# Pots.net
KiCad netlist of a schematic drawn in EAGLE
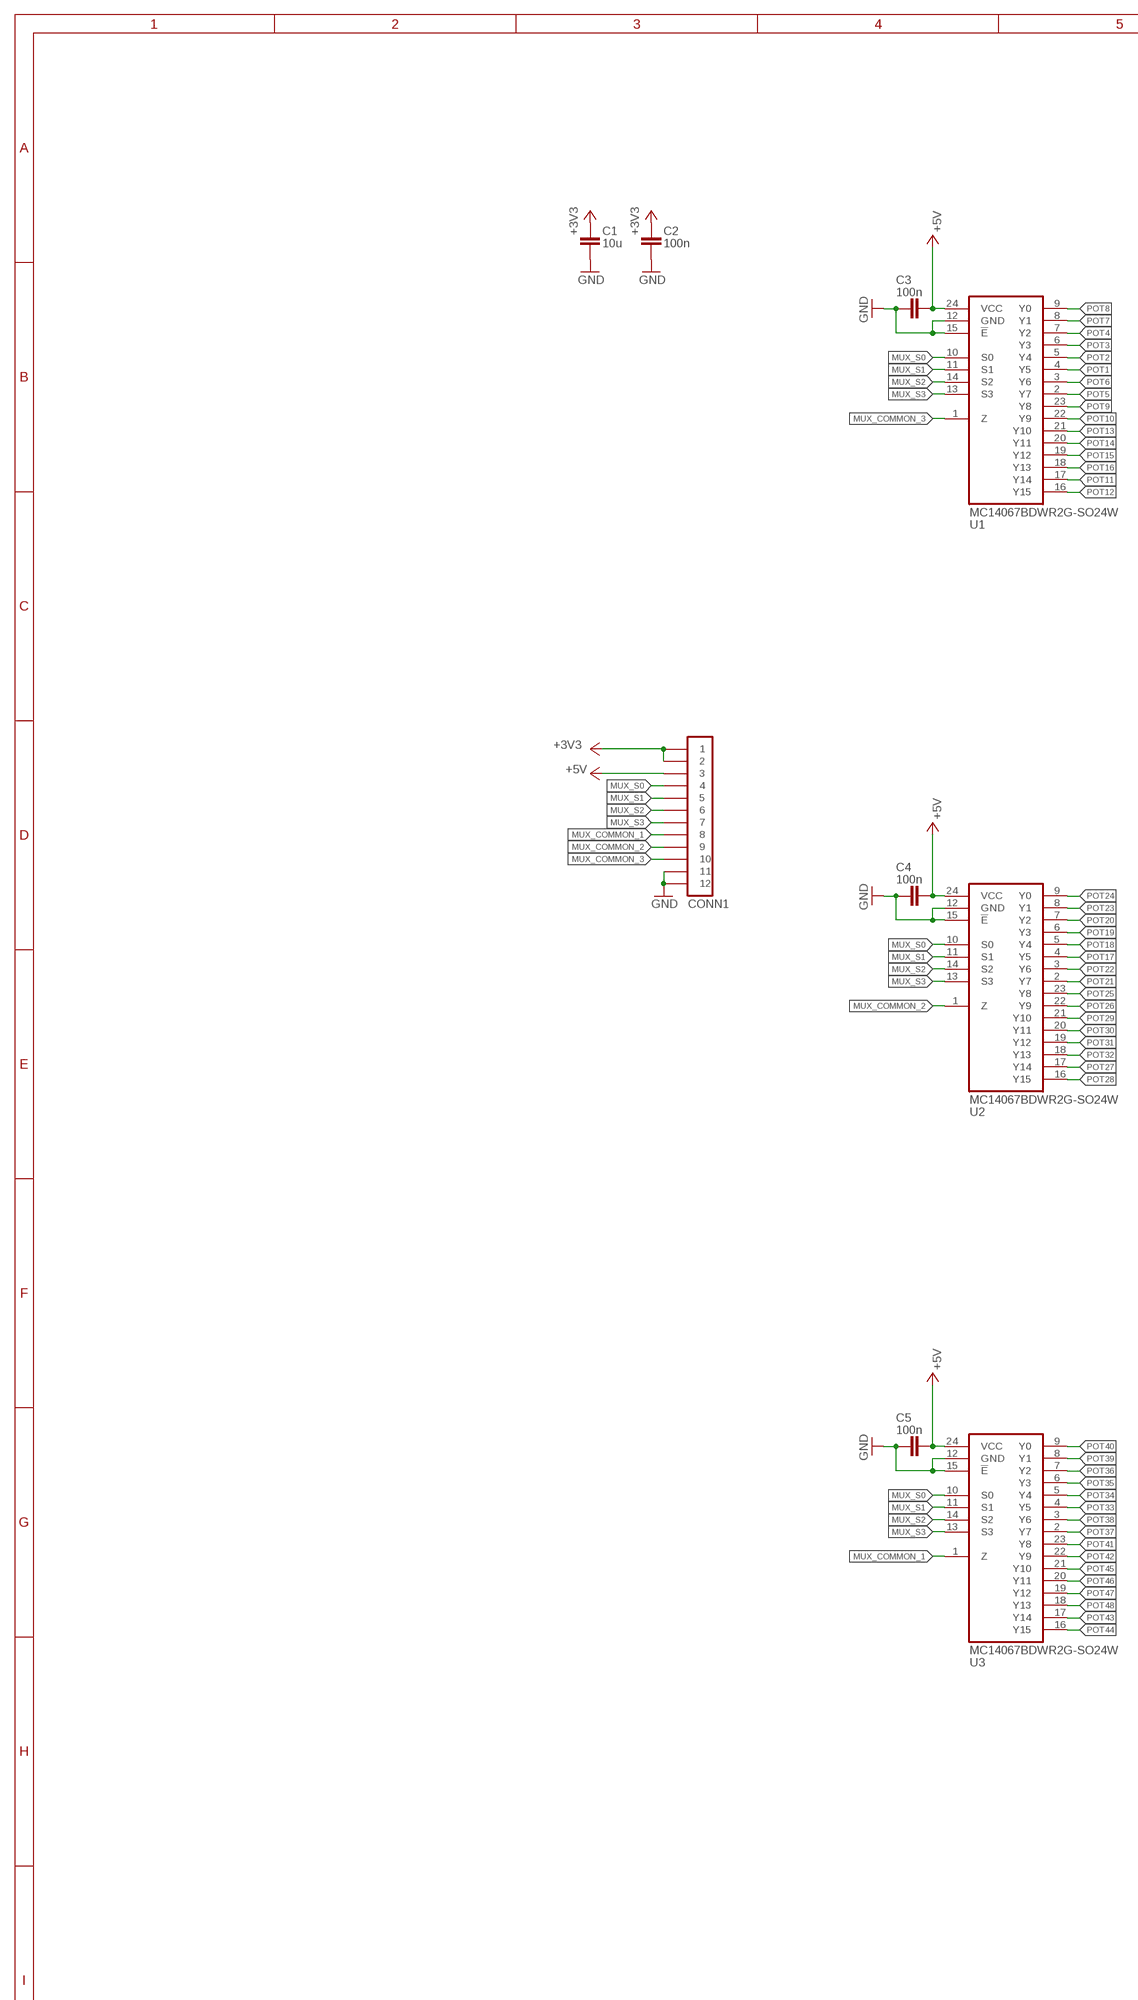
[diagram p0: schematic, sheet 1, part 1 of 2]
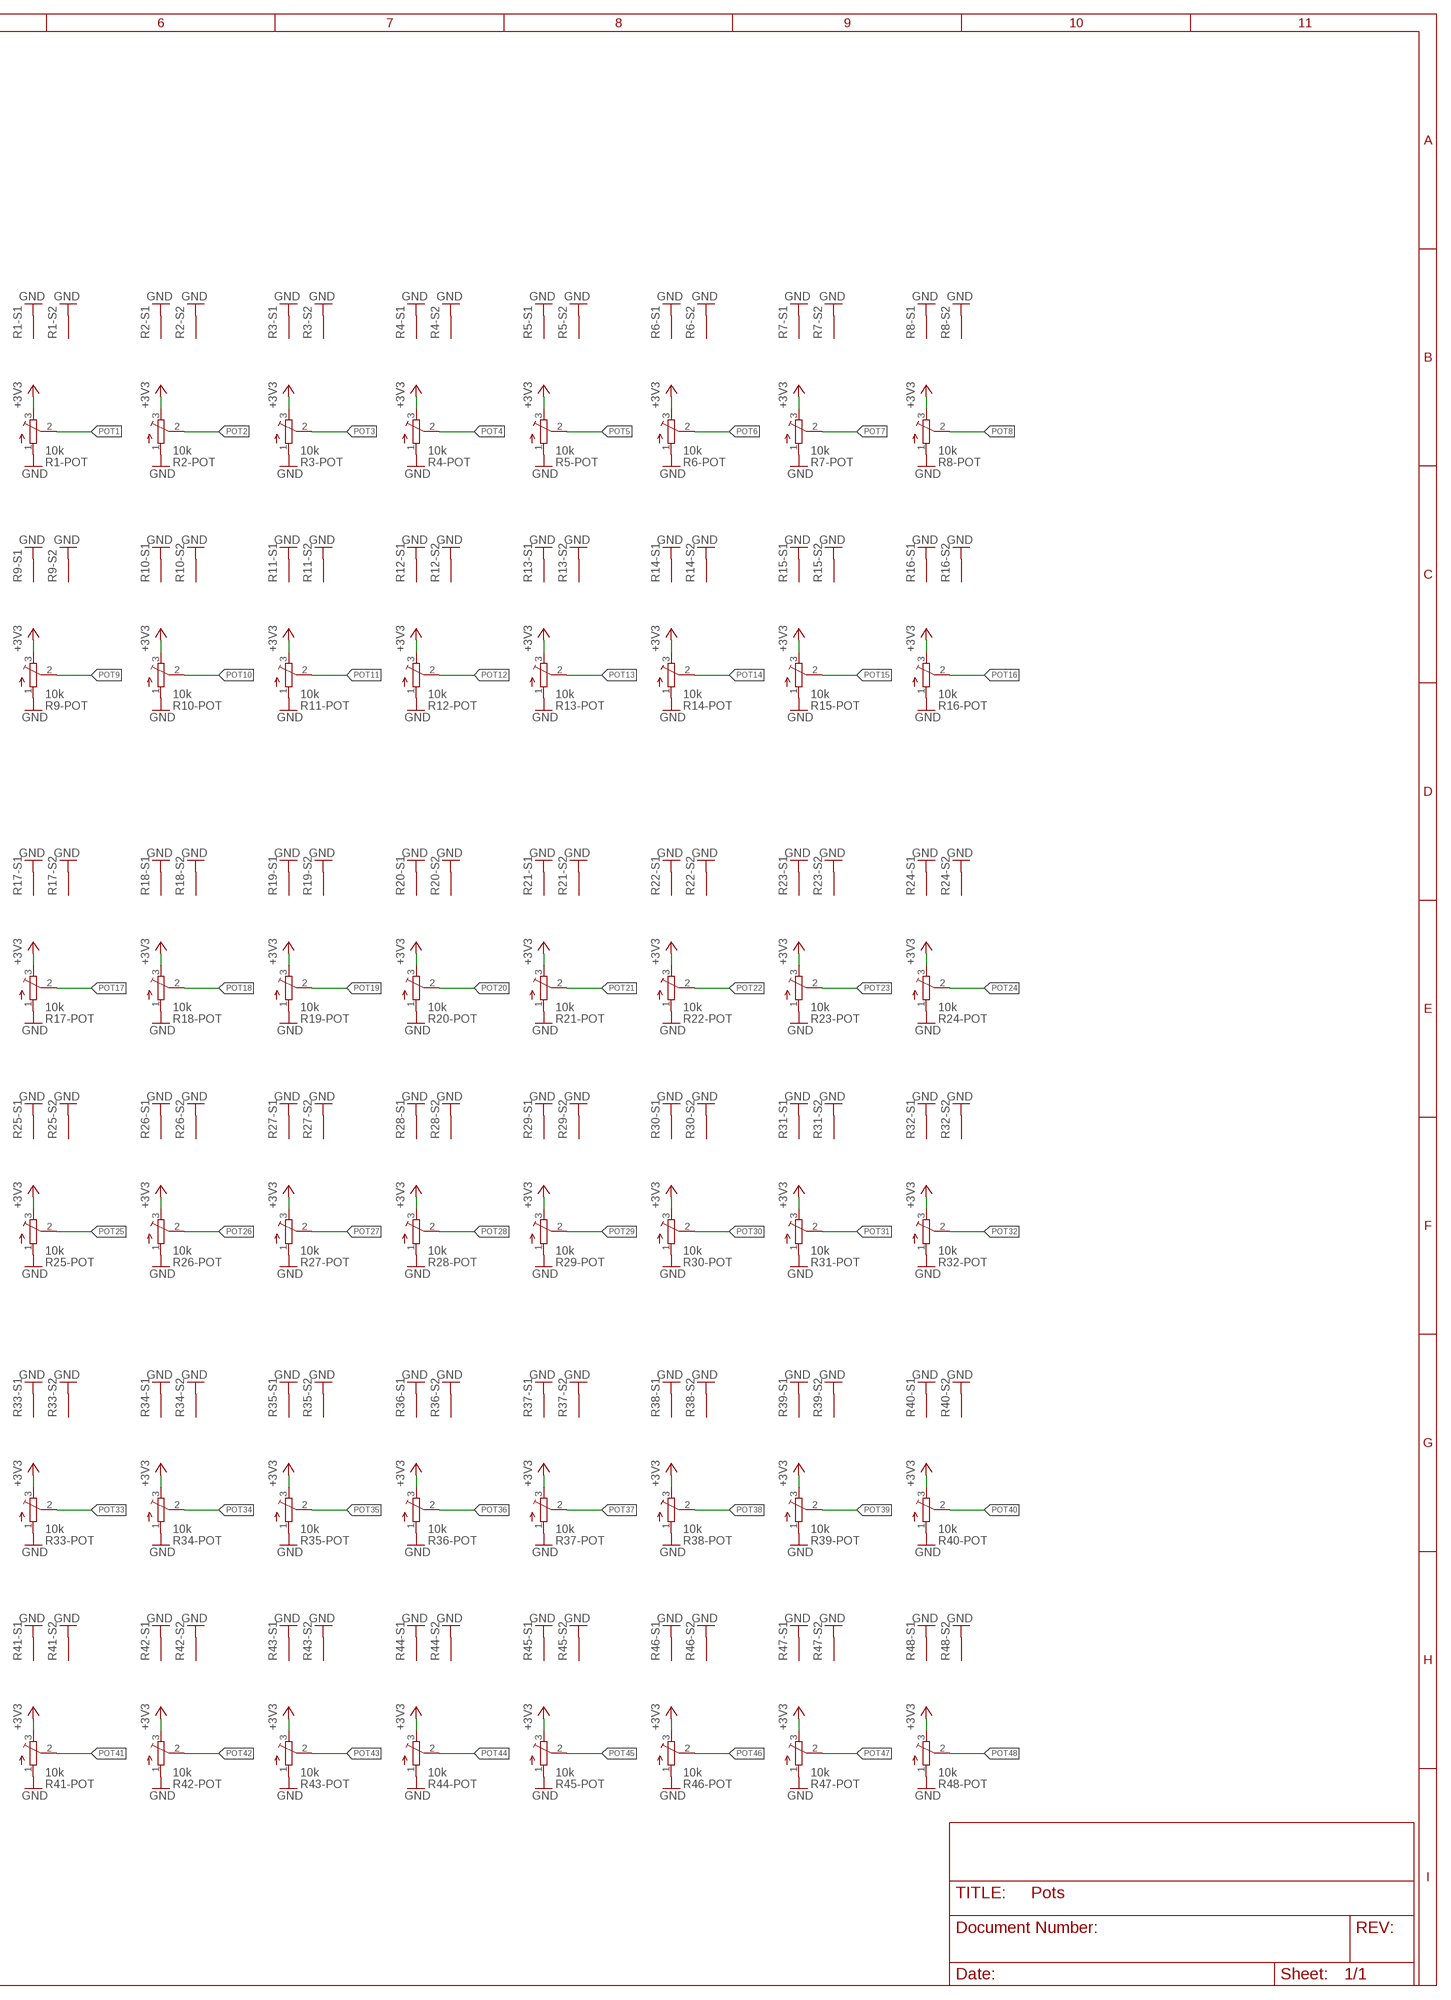
[diagram p1: schematic, sheet 1, part 2 of 2]

(export (version "E")
  (design (tool "Eeschema 10.0.6"))
  (components
    (comp (ref "C1")
      (value "10u")
      (footprint "eagle-import:C0805")
      (libsource (lib "eagle-import") (part "CAPACITOR-0805"))
    )
    (comp (ref "C2")
      (value "100n")
      (footprint "eagle-import:C0805")
      (libsource (lib "eagle-import") (part "CAPACITOR-0805"))
    )
    (comp (ref "C3")
      (value "100n")
      (footprint "eagle-import:C0805")
      (libsource (lib "eagle-import") (part "CAPACITOR-0805"))
    )
    (comp (ref "C4")
      (value "100n")
      (footprint "eagle-import:C0805")
      (libsource (lib "eagle-import") (part "CAPACITOR-0805"))
    )
    (comp (ref "C5")
      (value "100n")
      (footprint "eagle-import:C0805")
      (libsource (lib "eagle-import") (part "CAPACITOR-0805"))
    )
    (comp (ref "CONN1")
      (value "PINHD-1X12-SMD")
      (footprint "eagle-import:MOLEX-52271-1279")
      (fields (field (name "MANUFACTURER") "Molex") (field (name "MPN") "52271-1279"))
      (libsource (lib "eagle-import") (part "PINHD-1X12-SMD"))
    )
    (comp (ref "R1")
      (value "10k")
      (footprint "eagle-import:PTV09A-4025F-B103")
      (libsource (lib "eagle-import") (part "PTV09A-4025F-B103"))
    )
    (comp (ref "R2")
      (value "10k")
      (footprint "eagle-import:PTV09A-4025F-B103")
      (libsource (lib "eagle-import") (part "PTV09A-4025F-B103"))
    )
    (comp (ref "R3")
      (value "10k")
      (footprint "eagle-import:PTV09A-4025F-B103")
      (libsource (lib "eagle-import") (part "PTV09A-4025F-B103"))
    )
    (comp (ref "R4")
      (value "10k")
      (footprint "eagle-import:PTV09A-4025F-B103")
      (libsource (lib "eagle-import") (part "PTV09A-4025F-B103"))
    )
    (comp (ref "R5")
      (value "10k")
      (footprint "eagle-import:PTV09A-4025F-B103")
      (libsource (lib "eagle-import") (part "PTV09A-4025F-B103"))
    )
    (comp (ref "R6")
      (value "10k")
      (footprint "eagle-import:PTV09A-4025F-B103")
      (libsource (lib "eagle-import") (part "PTV09A-4025F-B103"))
    )
    (comp (ref "R7")
      (value "10k")
      (footprint "eagle-import:PTV09A-4025F-B103")
      (libsource (lib "eagle-import") (part "PTV09A-4025F-B103"))
    )
    (comp (ref "R8")
      (value "10k")
      (footprint "eagle-import:PTV09A-4025F-B103")
      (libsource (lib "eagle-import") (part "PTV09A-4025F-B103"))
    )
    (comp (ref "R9")
      (value "10k")
      (footprint "eagle-import:PTV09A-4025F-B103")
      (libsource (lib "eagle-import") (part "PTV09A-4025F-B103"))
    )
    (comp (ref "R10")
      (value "10k")
      (footprint "eagle-import:PTV09A-4025F-B103")
      (libsource (lib "eagle-import") (part "PTV09A-4025F-B103"))
    )
    (comp (ref "R11")
      (value "10k")
      (footprint "eagle-import:PTV09A-4025F-B103")
      (libsource (lib "eagle-import") (part "PTV09A-4025F-B103"))
    )
    (comp (ref "R12")
      (value "10k")
      (footprint "eagle-import:PTV09A-4025F-B103")
      (libsource (lib "eagle-import") (part "PTV09A-4025F-B103"))
    )
    (comp (ref "R13")
      (value "10k")
      (footprint "eagle-import:PTV09A-4025F-B103")
      (libsource (lib "eagle-import") (part "PTV09A-4025F-B103"))
    )
    (comp (ref "R14")
      (value "10k")
      (footprint "eagle-import:PTV09A-4025F-B103")
      (libsource (lib "eagle-import") (part "PTV09A-4025F-B103"))
    )
    (comp (ref "R15")
      (value "10k")
      (footprint "eagle-import:PTV09A-4025F-B103")
      (libsource (lib "eagle-import") (part "PTV09A-4025F-B103"))
    )
    (comp (ref "R16")
      (value "10k")
      (footprint "eagle-import:PTV09A-4025F-B103")
      (libsource (lib "eagle-import") (part "PTV09A-4025F-B103"))
    )
    (comp (ref "R17")
      (value "10k")
      (footprint "eagle-import:PTV09A-4025F-B103")
      (libsource (lib "eagle-import") (part "PTV09A-4025F-B103"))
    )
    (comp (ref "R18")
      (value "10k")
      (footprint "eagle-import:PTV09A-4025F-B103")
      (libsource (lib "eagle-import") (part "PTV09A-4025F-B103"))
    )
    (comp (ref "R19")
      (value "10k")
      (footprint "eagle-import:PTV09A-4025F-B103")
      (libsource (lib "eagle-import") (part "PTV09A-4025F-B103"))
    )
    (comp (ref "R20")
      (value "10k")
      (footprint "eagle-import:PTV09A-4025F-B103")
      (libsource (lib "eagle-import") (part "PTV09A-4025F-B103"))
    )
    (comp (ref "R21")
      (value "10k")
      (footprint "eagle-import:PTV09A-4025F-B103")
      (libsource (lib "eagle-import") (part "PTV09A-4025F-B103"))
    )
    (comp (ref "R22")
      (value "10k")
      (footprint "eagle-import:PTV09A-4025F-B103")
      (libsource (lib "eagle-import") (part "PTV09A-4025F-B103"))
    )
    (comp (ref "R23")
      (value "10k")
      (footprint "eagle-import:PTV09A-4025F-B103")
      (libsource (lib "eagle-import") (part "PTV09A-4025F-B103"))
    )
    (comp (ref "R24")
      (value "10k")
      (footprint "eagle-import:PTV09A-4025F-B103")
      (libsource (lib "eagle-import") (part "PTV09A-4025F-B103"))
    )
    (comp (ref "R25")
      (value "10k")
      (footprint "eagle-import:PTV09A-4025F-B103")
      (libsource (lib "eagle-import") (part "PTV09A-4025F-B103"))
    )
    (comp (ref "R26")
      (value "10k")
      (footprint "eagle-import:PTV09A-4025F-B103")
      (libsource (lib "eagle-import") (part "PTV09A-4025F-B103"))
    )
    (comp (ref "R27")
      (value "10k")
      (footprint "eagle-import:PTV09A-4025F-B103")
      (libsource (lib "eagle-import") (part "PTV09A-4025F-B103"))
    )
    (comp (ref "R28")
      (value "10k")
      (footprint "eagle-import:PTV09A-4025F-B103")
      (libsource (lib "eagle-import") (part "PTV09A-4025F-B103"))
    )
    (comp (ref "R29")
      (value "10k")
      (footprint "eagle-import:PTV09A-4025F-B103")
      (libsource (lib "eagle-import") (part "PTV09A-4025F-B103"))
    )
    (comp (ref "R30")
      (value "10k")
      (footprint "eagle-import:PTV09A-4025F-B103")
      (libsource (lib "eagle-import") (part "PTV09A-4025F-B103"))
    )
    (comp (ref "R31")
      (value "10k")
      (footprint "eagle-import:PTV09A-4025F-B103")
      (libsource (lib "eagle-import") (part "PTV09A-4025F-B103"))
    )
    (comp (ref "R32")
      (value "10k")
      (footprint "eagle-import:PTV09A-4025F-B103")
      (libsource (lib "eagle-import") (part "PTV09A-4025F-B103"))
    )
    (comp (ref "R33")
      (value "10k")
      (footprint "eagle-import:PTV09A-4025F-B103")
      (libsource (lib "eagle-import") (part "PTV09A-4025F-B103"))
    )
    (comp (ref "R34")
      (value "10k")
      (footprint "eagle-import:PTV09A-4025F-B103")
      (libsource (lib "eagle-import") (part "PTV09A-4025F-B103"))
    )
    (comp (ref "R35")
      (value "10k")
      (footprint "eagle-import:PTV09A-4025F-B103")
      (libsource (lib "eagle-import") (part "PTV09A-4025F-B103"))
    )
    (comp (ref "R36")
      (value "10k")
      (footprint "eagle-import:PTV09A-4025F-B103")
      (libsource (lib "eagle-import") (part "PTV09A-4025F-B103"))
    )
    (comp (ref "R37")
      (value "10k")
      (footprint "eagle-import:PTV09A-4025F-B103")
      (libsource (lib "eagle-import") (part "PTV09A-4025F-B103"))
    )
    (comp (ref "R38")
      (value "10k")
      (footprint "eagle-import:PTV09A-4025F-B103")
      (libsource (lib "eagle-import") (part "PTV09A-4025F-B103"))
    )
    (comp (ref "R39")
      (value "10k")
      (footprint "eagle-import:PTV09A-4025F-B103")
      (libsource (lib "eagle-import") (part "PTV09A-4025F-B103"))
    )
    (comp (ref "R40")
      (value "10k")
      (footprint "eagle-import:PTV09A-4025F-B103")
      (libsource (lib "eagle-import") (part "PTV09A-4025F-B103"))
    )
    (comp (ref "R41")
      (value "10k")
      (footprint "eagle-import:PTV09A-4025F-B103")
      (libsource (lib "eagle-import") (part "PTV09A-4025F-B103"))
    )
    (comp (ref "R42")
      (value "10k")
      (footprint "eagle-import:PTV09A-4025F-B103")
      (libsource (lib "eagle-import") (part "PTV09A-4025F-B103"))
    )
    (comp (ref "R43")
      (value "10k")
      (footprint "eagle-import:PTV09A-4025F-B103")
      (libsource (lib "eagle-import") (part "PTV09A-4025F-B103"))
    )
    (comp (ref "R44")
      (value "10k")
      (footprint "eagle-import:PTV09A-4025F-B103")
      (libsource (lib "eagle-import") (part "PTV09A-4025F-B103"))
    )
    (comp (ref "R45")
      (value "10k")
      (footprint "eagle-import:PTV09A-4025F-B103")
      (libsource (lib "eagle-import") (part "PTV09A-4025F-B103"))
    )
    (comp (ref "R46")
      (value "10k")
      (footprint "eagle-import:PTV09A-4025F-B103")
      (libsource (lib "eagle-import") (part "PTV09A-4025F-B103"))
    )
    (comp (ref "R47")
      (value "10k")
      (footprint "eagle-import:PTV09A-4025F-B103")
      (libsource (lib "eagle-import") (part "PTV09A-4025F-B103"))
    )
    (comp (ref "R48")
      (value "10k")
      (footprint "eagle-import:PTV09A-4025F-B103")
      (libsource (lib "eagle-import") (part "PTV09A-4025F-B103"))
    )
    (comp (ref "U1")
      (value "MC14067BDWR2G-SO24W")
      (footprint "eagle-import:SO24-W")
      (fields (field (name "MANUFACTURER") "ON Semiconductor") (field (name "MPN") "MC14067BDWR2G"))
      (libsource (lib "eagle-import") (part "MC14067BDWR2G-SO24W"))
    )
    (comp (ref "U2")
      (value "MC14067BDWR2G-SO24W")
      (footprint "eagle-import:SO24-W")
      (fields (field (name "MANUFACTURER") "ON Semiconductor") (field (name "MPN") "MC14067BDWR2G"))
      (libsource (lib "eagle-import") (part "MC14067BDWR2G-SO24W"))
    )
    (comp (ref "U3")
      (value "MC14067BDWR2G-SO24W")
      (footprint "eagle-import:SO24-W")
      (fields (field (name "MANUFACTURER") "ON Semiconductor") (field (name "MPN") "MC14067BDWR2G"))
      (libsource (lib "eagle-import") (part "MC14067BDWR2G-SO24W"))
    )
  )
  (nets
    (net (code "1") (name "+3V3") (class "Default")
      (node (ref "C1") (pin "1") (pinfunction "1_1") (pintype "passive"))
      (node (ref "C2") (pin "1") (pinfunction "1_1") (pintype "passive"))
      (node (ref "CONN1") (pin "1") (pinfunction "1_1") (pintype "passive"))
      (node (ref "CONN1") (pin "2") (pinfunction "2_2") (pintype "passive"))
      (node (ref "R1") (pin "3") (pinfunction "3_3") (pintype "passive"))
      (node (ref "R10") (pin "3") (pinfunction "3_3") (pintype "passive"))
      (node (ref "R11") (pin "3") (pinfunction "3_3") (pintype "passive"))
      (node (ref "R12") (pin "3") (pinfunction "3_3") (pintype "passive"))
      (node (ref "R13") (pin "3") (pinfunction "3_3") (pintype "passive"))
      (node (ref "R14") (pin "3") (pinfunction "3_3") (pintype "passive"))
      (node (ref "R15") (pin "3") (pinfunction "3_3") (pintype "passive"))
      (node (ref "R16") (pin "3") (pinfunction "3_3") (pintype "passive"))
      (node (ref "R17") (pin "3") (pinfunction "3_3") (pintype "passive"))
      (node (ref "R18") (pin "3") (pinfunction "3_3") (pintype "passive"))
      (node (ref "R19") (pin "3") (pinfunction "3_3") (pintype "passive"))
      (node (ref "R2") (pin "3") (pinfunction "3_3") (pintype "passive"))
      (node (ref "R20") (pin "3") (pinfunction "3_3") (pintype "passive"))
      (node (ref "R21") (pin "3") (pinfunction "3_3") (pintype "passive"))
      (node (ref "R22") (pin "3") (pinfunction "3_3") (pintype "passive"))
      (node (ref "R23") (pin "3") (pinfunction "3_3") (pintype "passive"))
      (node (ref "R24") (pin "3") (pinfunction "3_3") (pintype "passive"))
      (node (ref "R25") (pin "3") (pinfunction "3_3") (pintype "passive"))
      (node (ref "R26") (pin "3") (pinfunction "3_3") (pintype "passive"))
      (node (ref "R27") (pin "3") (pinfunction "3_3") (pintype "passive"))
      (node (ref "R28") (pin "3") (pinfunction "3_3") (pintype "passive"))
      (node (ref "R29") (pin "3") (pinfunction "3_3") (pintype "passive"))
      (node (ref "R3") (pin "3") (pinfunction "3_3") (pintype "passive"))
      (node (ref "R30") (pin "3") (pinfunction "3_3") (pintype "passive"))
      (node (ref "R31") (pin "3") (pinfunction "3_3") (pintype "passive"))
      (node (ref "R32") (pin "3") (pinfunction "3_3") (pintype "passive"))
      (node (ref "R33") (pin "3") (pinfunction "3_3") (pintype "passive"))
      (node (ref "R34") (pin "3") (pinfunction "3_3") (pintype "passive"))
      (node (ref "R35") (pin "3") (pinfunction "3_3") (pintype "passive"))
      (node (ref "R36") (pin "3") (pinfunction "3_3") (pintype "passive"))
      (node (ref "R37") (pin "3") (pinfunction "3_3") (pintype "passive"))
      (node (ref "R38") (pin "3") (pinfunction "3_3") (pintype "passive"))
      (node (ref "R39") (pin "3") (pinfunction "3_3") (pintype "passive"))
      (node (ref "R4") (pin "3") (pinfunction "3_3") (pintype "passive"))
      (node (ref "R40") (pin "3") (pinfunction "3_3") (pintype "passive"))
      (node (ref "R41") (pin "3") (pinfunction "3_3") (pintype "passive"))
      (node (ref "R42") (pin "3") (pinfunction "3_3") (pintype "passive"))
      (node (ref "R43") (pin "3") (pinfunction "3_3") (pintype "passive"))
      (node (ref "R44") (pin "3") (pinfunction "3_3") (pintype "passive"))
      (node (ref "R45") (pin "3") (pinfunction "3_3") (pintype "passive"))
      (node (ref "R46") (pin "3") (pinfunction "3_3") (pintype "passive"))
      (node (ref "R47") (pin "3") (pinfunction "3_3") (pintype "passive"))
      (node (ref "R48") (pin "3") (pinfunction "3_3") (pintype "passive"))
      (node (ref "R5") (pin "3") (pinfunction "3_3") (pintype "passive"))
      (node (ref "R6") (pin "3") (pinfunction "3_3") (pintype "passive"))
      (node (ref "R7") (pin "3") (pinfunction "3_3") (pintype "passive"))
      (node (ref "R8") (pin "3") (pinfunction "3_3") (pintype "passive"))
      (node (ref "R9") (pin "3") (pinfunction "3_3") (pintype "passive"))
    )
    (net (code "2") (name "+5V") (class "Default")
      (node (ref "C3") (pin "2") (pinfunction "2_2") (pintype "passive"))
      (node (ref "C4") (pin "2") (pinfunction "2_2") (pintype "passive"))
      (node (ref "C5") (pin "2") (pinfunction "2_2") (pintype "passive"))
      (node (ref "CONN1") (pin "3") (pinfunction "3_3") (pintype "passive"))
      (node (ref "U1") (pin "24") (pinfunction "VCC_24") (pintype "passive"))
      (node (ref "U2") (pin "24") (pinfunction "VCC_24") (pintype "passive"))
      (node (ref "U3") (pin "24") (pinfunction "VCC_24") (pintype "passive"))
    )
    (net (code "3") (name "GND") (class "Default")
      (node (ref "C1") (pin "2") (pinfunction "2_2") (pintype "passive"))
      (node (ref "C2") (pin "2") (pinfunction "2_2") (pintype "passive"))
      (node (ref "C3") (pin "1") (pinfunction "1_1") (pintype "passive"))
      (node (ref "C4") (pin "1") (pinfunction "1_1") (pintype "passive"))
      (node (ref "C5") (pin "1") (pinfunction "1_1") (pintype "passive"))
      (node (ref "CONN1") (pin "11") (pinfunction "11_11") (pintype "passive"))
      (node (ref "CONN1") (pin "12") (pinfunction "12_12") (pintype "passive"))
      (node (ref "R1") (pin "1") (pinfunction "1_1") (pintype "passive"))
      (node (ref "R1") (pin "S1") (pinfunction "S_S1") (pintype "passive"))
      (node (ref "R1") (pin "S2") (pinfunction "S_S2") (pintype "passive"))
      (node (ref "R10") (pin "1") (pinfunction "1_1") (pintype "passive"))
      (node (ref "R10") (pin "S1") (pinfunction "S_S1") (pintype "passive"))
      (node (ref "R10") (pin "S2") (pinfunction "S_S2") (pintype "passive"))
      (node (ref "R11") (pin "1") (pinfunction "1_1") (pintype "passive"))
      (node (ref "R11") (pin "S1") (pinfunction "S_S1") (pintype "passive"))
      (node (ref "R11") (pin "S2") (pinfunction "S_S2") (pintype "passive"))
      (node (ref "R12") (pin "1") (pinfunction "1_1") (pintype "passive"))
      (node (ref "R12") (pin "S1") (pinfunction "S_S1") (pintype "passive"))
      (node (ref "R12") (pin "S2") (pinfunction "S_S2") (pintype "passive"))
      (node (ref "R13") (pin "1") (pinfunction "1_1") (pintype "passive"))
      (node (ref "R13") (pin "S1") (pinfunction "S_S1") (pintype "passive"))
      (node (ref "R13") (pin "S2") (pinfunction "S_S2") (pintype "passive"))
      (node (ref "R14") (pin "1") (pinfunction "1_1") (pintype "passive"))
      (node (ref "R14") (pin "S1") (pinfunction "S_S1") (pintype "passive"))
      (node (ref "R14") (pin "S2") (pinfunction "S_S2") (pintype "passive"))
      (node (ref "R15") (pin "1") (pinfunction "1_1") (pintype "passive"))
      (node (ref "R15") (pin "S1") (pinfunction "S_S1") (pintype "passive"))
      (node (ref "R15") (pin "S2") (pinfunction "S_S2") (pintype "passive"))
      (node (ref "R16") (pin "1") (pinfunction "1_1") (pintype "passive"))
      (node (ref "R16") (pin "S1") (pinfunction "S_S1") (pintype "passive"))
      (node (ref "R16") (pin "S2") (pinfunction "S_S2") (pintype "passive"))
      (node (ref "R17") (pin "1") (pinfunction "1_1") (pintype "passive"))
      (node (ref "R17") (pin "S1") (pinfunction "S_S1") (pintype "passive"))
      (node (ref "R17") (pin "S2") (pinfunction "S_S2") (pintype "passive"))
      (node (ref "R18") (pin "1") (pinfunction "1_1") (pintype "passive"))
      (node (ref "R18") (pin "S1") (pinfunction "S_S1") (pintype "passive"))
      (node (ref "R18") (pin "S2") (pinfunction "S_S2") (pintype "passive"))
      (node (ref "R19") (pin "1") (pinfunction "1_1") (pintype "passive"))
      (node (ref "R19") (pin "S1") (pinfunction "S_S1") (pintype "passive"))
      (node (ref "R19") (pin "S2") (pinfunction "S_S2") (pintype "passive"))
      (node (ref "R2") (pin "1") (pinfunction "1_1") (pintype "passive"))
      (node (ref "R2") (pin "S1") (pinfunction "S_S1") (pintype "passive"))
      (node (ref "R2") (pin "S2") (pinfunction "S_S2") (pintype "passive"))
      (node (ref "R20") (pin "1") (pinfunction "1_1") (pintype "passive"))
      (node (ref "R20") (pin "S1") (pinfunction "S_S1") (pintype "passive"))
      (node (ref "R20") (pin "S2") (pinfunction "S_S2") (pintype "passive"))
      (node (ref "R21") (pin "1") (pinfunction "1_1") (pintype "passive"))
      (node (ref "R21") (pin "S1") (pinfunction "S_S1") (pintype "passive"))
      (node (ref "R21") (pin "S2") (pinfunction "S_S2") (pintype "passive"))
      (node (ref "R22") (pin "1") (pinfunction "1_1") (pintype "passive"))
      (node (ref "R22") (pin "S1") (pinfunction "S_S1") (pintype "passive"))
      (node (ref "R22") (pin "S2") (pinfunction "S_S2") (pintype "passive"))
      (node (ref "R23") (pin "1") (pinfunction "1_1") (pintype "passive"))
      (node (ref "R23") (pin "S1") (pinfunction "S_S1") (pintype "passive"))
      (node (ref "R23") (pin "S2") (pinfunction "S_S2") (pintype "passive"))
      (node (ref "R24") (pin "1") (pinfunction "1_1") (pintype "passive"))
      (node (ref "R24") (pin "S1") (pinfunction "S_S1") (pintype "passive"))
      (node (ref "R24") (pin "S2") (pinfunction "S_S2") (pintype "passive"))
      (node (ref "R25") (pin "1") (pinfunction "1_1") (pintype "passive"))
      (node (ref "R25") (pin "S1") (pinfunction "S_S1") (pintype "passive"))
      (node (ref "R25") (pin "S2") (pinfunction "S_S2") (pintype "passive"))
      (node (ref "R26") (pin "1") (pinfunction "1_1") (pintype "passive"))
      (node (ref "R26") (pin "S1") (pinfunction "S_S1") (pintype "passive"))
      (node (ref "R26") (pin "S2") (pinfunction "S_S2") (pintype "passive"))
      (node (ref "R27") (pin "1") (pinfunction "1_1") (pintype "passive"))
      (node (ref "R27") (pin "S1") (pinfunction "S_S1") (pintype "passive"))
      (node (ref "R27") (pin "S2") (pinfunction "S_S2") (pintype "passive"))
      (node (ref "R28") (pin "1") (pinfunction "1_1") (pintype "passive"))
      (node (ref "R28") (pin "S1") (pinfunction "S_S1") (pintype "passive"))
      (node (ref "R28") (pin "S2") (pinfunction "S_S2") (pintype "passive"))
      (node (ref "R29") (pin "1") (pinfunction "1_1") (pintype "passive"))
      (node (ref "R29") (pin "S1") (pinfunction "S_S1") (pintype "passive"))
      (node (ref "R29") (pin "S2") (pinfunction "S_S2") (pintype "passive"))
      (node (ref "R3") (pin "1") (pinfunction "1_1") (pintype "passive"))
      (node (ref "R3") (pin "S1") (pinfunction "S_S1") (pintype "passive"))
      (node (ref "R3") (pin "S2") (pinfunction "S_S2") (pintype "passive"))
      (node (ref "R30") (pin "1") (pinfunction "1_1") (pintype "passive"))
      (node (ref "R30") (pin "S1") (pinfunction "S_S1") (pintype "passive"))
      (node (ref "R30") (pin "S2") (pinfunction "S_S2") (pintype "passive"))
      (node (ref "R31") (pin "1") (pinfunction "1_1") (pintype "passive"))
      (node (ref "R31") (pin "S1") (pinfunction "S_S1") (pintype "passive"))
      (node (ref "R31") (pin "S2") (pinfunction "S_S2") (pintype "passive"))
      (node (ref "R32") (pin "1") (pinfunction "1_1") (pintype "passive"))
      (node (ref "R32") (pin "S1") (pinfunction "S_S1") (pintype "passive"))
      (node (ref "R32") (pin "S2") (pinfunction "S_S2") (pintype "passive"))
      (node (ref "R33") (pin "1") (pinfunction "1_1") (pintype "passive"))
      (node (ref "R33") (pin "S1") (pinfunction "S_S1") (pintype "passive"))
      (node (ref "R33") (pin "S2") (pinfunction "S_S2") (pintype "passive"))
      (node (ref "R34") (pin "1") (pinfunction "1_1") (pintype "passive"))
      (node (ref "R34") (pin "S1") (pinfunction "S_S1") (pintype "passive"))
      (node (ref "R34") (pin "S2") (pinfunction "S_S2") (pintype "passive"))
      (node (ref "R35") (pin "1") (pinfunction "1_1") (pintype "passive"))
      (node (ref "R35") (pin "S1") (pinfunction "S_S1") (pintype "passive"))
      (node (ref "R35") (pin "S2") (pinfunction "S_S2") (pintype "passive"))
      (node (ref "R36") (pin "1") (pinfunction "1_1") (pintype "passive"))
      (node (ref "R36") (pin "S1") (pinfunction "S_S1") (pintype "passive"))
      (node (ref "R36") (pin "S2") (pinfunction "S_S2") (pintype "passive"))
      (node (ref "R37") (pin "1") (pinfunction "1_1") (pintype "passive"))
      (node (ref "R37") (pin "S1") (pinfunction "S_S1") (pintype "passive"))
      (node (ref "R37") (pin "S2") (pinfunction "S_S2") (pintype "passive"))
      (node (ref "R38") (pin "1") (pinfunction "1_1") (pintype "passive"))
      (node (ref "R38") (pin "S1") (pinfunction "S_S1") (pintype "passive"))
      (node (ref "R38") (pin "S2") (pinfunction "S_S2") (pintype "passive"))
      (node (ref "R39") (pin "1") (pinfunction "1_1") (pintype "passive"))
      (node (ref "R39") (pin "S1") (pinfunction "S_S1") (pintype "passive"))
      (node (ref "R39") (pin "S2") (pinfunction "S_S2") (pintype "passive"))
      (node (ref "R4") (pin "1") (pinfunction "1_1") (pintype "passive"))
      (node (ref "R4") (pin "S1") (pinfunction "S_S1") (pintype "passive"))
      (node (ref "R4") (pin "S2") (pinfunction "S_S2") (pintype "passive"))
      (node (ref "R40") (pin "1") (pinfunction "1_1") (pintype "passive"))
      (node (ref "R40") (pin "S1") (pinfunction "S_S1") (pintype "passive"))
      (node (ref "R40") (pin "S2") (pinfunction "S_S2") (pintype "passive"))
      (node (ref "R41") (pin "1") (pinfunction "1_1") (pintype "passive"))
      (node (ref "R41") (pin "S1") (pinfunction "S_S1") (pintype "passive"))
      (node (ref "R41") (pin "S2") (pinfunction "S_S2") (pintype "passive"))
      (node (ref "R42") (pin "1") (pinfunction "1_1") (pintype "passive"))
      (node (ref "R42") (pin "S1") (pinfunction "S_S1") (pintype "passive"))
      (node (ref "R42") (pin "S2") (pinfunction "S_S2") (pintype "passive"))
      (node (ref "R43") (pin "1") (pinfunction "1_1") (pintype "passive"))
      (node (ref "R43") (pin "S1") (pinfunction "S_S1") (pintype "passive"))
      (node (ref "R43") (pin "S2") (pinfunction "S_S2") (pintype "passive"))
      (node (ref "R44") (pin "1") (pinfunction "1_1") (pintype "passive"))
      (node (ref "R44") (pin "S1") (pinfunction "S_S1") (pintype "passive"))
      (node (ref "R44") (pin "S2") (pinfunction "S_S2") (pintype "passive"))
      (node (ref "R45") (pin "1") (pinfunction "1_1") (pintype "passive"))
      (node (ref "R45") (pin "S1") (pinfunction "S_S1") (pintype "passive"))
      (node (ref "R45") (pin "S2") (pinfunction "S_S2") (pintype "passive"))
      (node (ref "R46") (pin "1") (pinfunction "1_1") (pintype "passive"))
      (node (ref "R46") (pin "S1") (pinfunction "S_S1") (pintype "passive"))
      (node (ref "R46") (pin "S2") (pinfunction "S_S2") (pintype "passive"))
      (node (ref "R47") (pin "1") (pinfunction "1_1") (pintype "passive"))
      (node (ref "R47") (pin "S1") (pinfunction "S_S1") (pintype "passive"))
      (node (ref "R47") (pin "S2") (pinfunction "S_S2") (pintype "passive"))
      (node (ref "R48") (pin "1") (pinfunction "1_1") (pintype "passive"))
      (node (ref "R48") (pin "S1") (pinfunction "S_S1") (pintype "passive"))
      (node (ref "R48") (pin "S2") (pinfunction "S_S2") (pintype "passive"))
      (node (ref "R5") (pin "1") (pinfunction "1_1") (pintype "passive"))
      (node (ref "R5") (pin "S1") (pinfunction "S_S1") (pintype "passive"))
      (node (ref "R5") (pin "S2") (pinfunction "S_S2") (pintype "passive"))
      (node (ref "R6") (pin "1") (pinfunction "1_1") (pintype "passive"))
      (node (ref "R6") (pin "S1") (pinfunction "S_S1") (pintype "passive"))
      (node (ref "R6") (pin "S2") (pinfunction "S_S2") (pintype "passive"))
      (node (ref "R7") (pin "1") (pinfunction "1_1") (pintype "passive"))
      (node (ref "R7") (pin "S1") (pinfunction "S_S1") (pintype "passive"))
      (node (ref "R7") (pin "S2") (pinfunction "S_S2") (pintype "passive"))
      (node (ref "R8") (pin "1") (pinfunction "1_1") (pintype "passive"))
      (node (ref "R8") (pin "S1") (pinfunction "S_S1") (pintype "passive"))
      (node (ref "R8") (pin "S2") (pinfunction "S_S2") (pintype "passive"))
      (node (ref "R9") (pin "1") (pinfunction "1_1") (pintype "passive"))
      (node (ref "R9") (pin "S1") (pinfunction "S_S1") (pintype "passive"))
      (node (ref "R9") (pin "S2") (pinfunction "S_S2") (pintype "passive"))
      (node (ref "U1") (pin "12") (pinfunction "GND_12") (pintype "passive"))
      (node (ref "U1") (pin "15") (pinfunction "~{E}_15") (pintype "input"))
      (node (ref "U2") (pin "12") (pinfunction "GND_12") (pintype "passive"))
      (node (ref "U2") (pin "15") (pinfunction "~{E}_15") (pintype "input"))
      (node (ref "U3") (pin "12") (pinfunction "GND_12") (pintype "passive"))
      (node (ref "U3") (pin "15") (pinfunction "~{E}_15") (pintype "input"))
    )
    (net (code "4") (name "MUX_COMMON_1") (class "Default")
      (node (ref "CONN1") (pin "8") (pinfunction "8_8") (pintype "passive"))
      (node (ref "U3") (pin "1") (pinfunction "Z_1") (pintype "bidirectional"))
    )
    (net (code "5") (name "MUX_COMMON_2") (class "Default")
      (node (ref "CONN1") (pin "9") (pinfunction "9_9") (pintype "passive"))
      (node (ref "U2") (pin "1") (pinfunction "Z_1") (pintype "bidirectional"))
    )
    (net (code "6") (name "MUX_COMMON_3") (class "Default")
      (node (ref "CONN1") (pin "10") (pinfunction "10_10") (pintype "passive"))
      (node (ref "U1") (pin "1") (pinfunction "Z_1") (pintype "bidirectional"))
    )
    (net (code "7") (name "MUX_S0") (class "Default")
      (node (ref "CONN1") (pin "4") (pinfunction "4_4") (pintype "passive"))
      (node (ref "U1") (pin "10") (pinfunction "S0_10") (pintype "input"))
      (node (ref "U2") (pin "10") (pinfunction "S0_10") (pintype "input"))
      (node (ref "U3") (pin "10") (pinfunction "S0_10") (pintype "input"))
    )
    (net (code "8") (name "MUX_S1") (class "Default")
      (node (ref "CONN1") (pin "5") (pinfunction "5_5") (pintype "passive"))
      (node (ref "U1") (pin "11") (pinfunction "S1_11") (pintype "input"))
      (node (ref "U2") (pin "11") (pinfunction "S1_11") (pintype "input"))
      (node (ref "U3") (pin "11") (pinfunction "S1_11") (pintype "input"))
    )
    (net (code "9") (name "MUX_S2") (class "Default")
      (node (ref "CONN1") (pin "6") (pinfunction "6_6") (pintype "passive"))
      (node (ref "U1") (pin "14") (pinfunction "S2_14") (pintype "input"))
      (node (ref "U2") (pin "14") (pinfunction "S2_14") (pintype "input"))
      (node (ref "U3") (pin "14") (pinfunction "S2_14") (pintype "input"))
    )
    (net (code "10") (name "MUX_S3") (class "Default")
      (node (ref "CONN1") (pin "7") (pinfunction "7_7") (pintype "passive"))
      (node (ref "U1") (pin "13") (pinfunction "S3_13") (pintype "input"))
      (node (ref "U2") (pin "13") (pinfunction "S3_13") (pintype "input"))
      (node (ref "U3") (pin "13") (pinfunction "S3_13") (pintype "input"))
    )
    (net (code "11") (name "POT1") (class "Default")
      (node (ref "R1") (pin "2") (pinfunction "2_2") (pintype "passive"))
      (node (ref "U1") (pin "4") (pinfunction "Y5_4") (pintype "bidirectional"))
    )
    (net (code "12") (name "POT2") (class "Default")
      (node (ref "R2") (pin "2") (pinfunction "2_2") (pintype "passive"))
      (node (ref "U1") (pin "5") (pinfunction "Y4_5") (pintype "bidirectional"))
    )
    (net (code "13") (name "POT3") (class "Default")
      (node (ref "R3") (pin "2") (pinfunction "2_2") (pintype "passive"))
      (node (ref "U1") (pin "6") (pinfunction "Y3_6") (pintype "bidirectional"))
    )
    (net (code "14") (name "POT4") (class "Default")
      (node (ref "R4") (pin "2") (pinfunction "2_2") (pintype "passive"))
      (node (ref "U1") (pin "7") (pinfunction "Y2_7") (pintype "bidirectional"))
    )
    (net (code "15") (name "POT5") (class "Default")
      (node (ref "R5") (pin "2") (pinfunction "2_2") (pintype "passive"))
      (node (ref "U1") (pin "2") (pinfunction "Y7_2") (pintype "bidirectional"))
    )
    (net (code "16") (name "POT6") (class "Default")
      (node (ref "R6") (pin "2") (pinfunction "2_2") (pintype "passive"))
      (node (ref "U1") (pin "3") (pinfunction "Y6_3") (pintype "bidirectional"))
    )
    (net (code "17") (name "POT7") (class "Default")
      (node (ref "R7") (pin "2") (pinfunction "2_2") (pintype "passive"))
      (node (ref "U1") (pin "8") (pinfunction "Y1_8") (pintype "bidirectional"))
    )
    (net (code "18") (name "POT8") (class "Default")
      (node (ref "R8") (pin "2") (pinfunction "2_2") (pintype "passive"))
      (node (ref "U1") (pin "9") (pinfunction "Y0_9") (pintype "bidirectional"))
    )
    (net (code "19") (name "POT9") (class "Default")
      (node (ref "R9") (pin "2") (pinfunction "2_2") (pintype "passive"))
      (node (ref "U1") (pin "23") (pinfunction "Y8_23") (pintype "bidirectional"))
    )
    (net (code "20") (name "POT10") (class "Default")
      (node (ref "R10") (pin "2") (pinfunction "2_2") (pintype "passive"))
      (node (ref "U1") (pin "22") (pinfunction "Y9_22") (pintype "bidirectional"))
    )
    (net (code "21") (name "POT11") (class "Default")
      (node (ref "R11") (pin "2") (pinfunction "2_2") (pintype "passive"))
      (node (ref "U1") (pin "17") (pinfunction "Y14_17") (pintype "bidirectional"))
    )
    (net (code "22") (name "POT12") (class "Default")
      (node (ref "R12") (pin "2") (pinfunction "2_2") (pintype "passive"))
      (node (ref "U1") (pin "16") (pinfunction "Y15_16") (pintype "bidirectional"))
    )
    (net (code "23") (name "POT13") (class "Default")
      (node (ref "R13") (pin "2") (pinfunction "2_2") (pintype "passive"))
      (node (ref "U1") (pin "21") (pinfunction "Y10_21") (pintype "bidirectional"))
    )
    (net (code "24") (name "POT14") (class "Default")
      (node (ref "R14") (pin "2") (pinfunction "2_2") (pintype "passive"))
      (node (ref "U1") (pin "20") (pinfunction "Y11_20") (pintype "bidirectional"))
    )
    (net (code "25") (name "POT15") (class "Default")
      (node (ref "R15") (pin "2") (pinfunction "2_2") (pintype "passive"))
      (node (ref "U1") (pin "19") (pinfunction "Y12_19") (pintype "bidirectional"))
    )
    (net (code "26") (name "POT16") (class "Default")
      (node (ref "R16") (pin "2") (pinfunction "2_2") (pintype "passive"))
      (node (ref "U1") (pin "18") (pinfunction "Y13_18") (pintype "bidirectional"))
    )
    (net (code "27") (name "POT17") (class "Default")
      (node (ref "R17") (pin "2") (pinfunction "2_2") (pintype "passive"))
      (node (ref "U2") (pin "4") (pinfunction "Y5_4") (pintype "bidirectional"))
    )
    (net (code "28") (name "POT18") (class "Default")
      (node (ref "R18") (pin "2") (pinfunction "2_2") (pintype "passive"))
      (node (ref "U2") (pin "5") (pinfunction "Y4_5") (pintype "bidirectional"))
    )
    (net (code "29") (name "POT19") (class "Default")
      (node (ref "R19") (pin "2") (pinfunction "2_2") (pintype "passive"))
      (node (ref "U2") (pin "6") (pinfunction "Y3_6") (pintype "bidirectional"))
    )
    (net (code "30") (name "POT20") (class "Default")
      (node (ref "R20") (pin "2") (pinfunction "2_2") (pintype "passive"))
      (node (ref "U2") (pin "7") (pinfunction "Y2_7") (pintype "bidirectional"))
    )
    (net (code "31") (name "POT21") (class "Default")
      (node (ref "R21") (pin "2") (pinfunction "2_2") (pintype "passive"))
      (node (ref "U2") (pin "2") (pinfunction "Y7_2") (pintype "bidirectional"))
    )
    (net (code "32") (name "POT22") (class "Default")
      (node (ref "R22") (pin "2") (pinfunction "2_2") (pintype "passive"))
      (node (ref "U2") (pin "3") (pinfunction "Y6_3") (pintype "bidirectional"))
    )
    (net (code "33") (name "POT23") (class "Default")
      (node (ref "R23") (pin "2") (pinfunction "2_2") (pintype "passive"))
      (node (ref "U2") (pin "8") (pinfunction "Y1_8") (pintype "bidirectional"))
    )
    (net (code "34") (name "POT24") (class "Default")
      (node (ref "R24") (pin "2") (pinfunction "2_2") (pintype "passive"))
      (node (ref "U2") (pin "9") (pinfunction "Y0_9") (pintype "bidirectional"))
    )
    (net (code "35") (name "POT25") (class "Default")
      (node (ref "R25") (pin "2") (pinfunction "2_2") (pintype "passive"))
      (node (ref "U2") (pin "23") (pinfunction "Y8_23") (pintype "bidirectional"))
    )
    (net (code "36") (name "POT26") (class "Default")
      (node (ref "R26") (pin "2") (pinfunction "2_2") (pintype "passive"))
      (node (ref "U2") (pin "22") (pinfunction "Y9_22") (pintype "bidirectional"))
    )
    (net (code "37") (name "POT27") (class "Default")
      (node (ref "R27") (pin "2") (pinfunction "2_2") (pintype "passive"))
      (node (ref "U2") (pin "17") (pinfunction "Y14_17") (pintype "bidirectional"))
    )
    (net (code "38") (name "POT28") (class "Default")
      (node (ref "R28") (pin "2") (pinfunction "2_2") (pintype "passive"))
      (node (ref "U2") (pin "16") (pinfunction "Y15_16") (pintype "bidirectional"))
    )
    (net (code "39") (name "POT29") (class "Default")
      (node (ref "R29") (pin "2") (pinfunction "2_2") (pintype "passive"))
      (node (ref "U2") (pin "21") (pinfunction "Y10_21") (pintype "bidirectional"))
    )
    (net (code "40") (name "POT30") (class "Default")
      (node (ref "R30") (pin "2") (pinfunction "2_2") (pintype "passive"))
      (node (ref "U2") (pin "20") (pinfunction "Y11_20") (pintype "bidirectional"))
    )
    (net (code "41") (name "POT31") (class "Default")
      (node (ref "R31") (pin "2") (pinfunction "2_2") (pintype "passive"))
      (node (ref "U2") (pin "19") (pinfunction "Y12_19") (pintype "bidirectional"))
    )
    (net (code "42") (name "POT32") (class "Default")
      (node (ref "R32") (pin "2") (pinfunction "2_2") (pintype "passive"))
      (node (ref "U2") (pin "18") (pinfunction "Y13_18") (pintype "bidirectional"))
    )
    (net (code "43") (name "POT33") (class "Default")
      (node (ref "R33") (pin "2") (pinfunction "2_2") (pintype "passive"))
      (node (ref "U3") (pin "4") (pinfunction "Y5_4") (pintype "bidirectional"))
    )
    (net (code "44") (name "POT34") (class "Default")
      (node (ref "R34") (pin "2") (pinfunction "2_2") (pintype "passive"))
      (node (ref "U3") (pin "5") (pinfunction "Y4_5") (pintype "bidirectional"))
    )
    (net (code "45") (name "POT35") (class "Default")
      (node (ref "R35") (pin "2") (pinfunction "2_2") (pintype "passive"))
      (node (ref "U3") (pin "6") (pinfunction "Y3_6") (pintype "bidirectional"))
    )
    (net (code "46") (name "POT36") (class "Default")
      (node (ref "R36") (pin "2") (pinfunction "2_2") (pintype "passive"))
      (node (ref "U3") (pin "7") (pinfunction "Y2_7") (pintype "bidirectional"))
    )
    (net (code "47") (name "POT37") (class "Default")
      (node (ref "R37") (pin "2") (pinfunction "2_2") (pintype "passive"))
      (node (ref "U3") (pin "2") (pinfunction "Y7_2") (pintype "bidirectional"))
    )
    (net (code "48") (name "POT38") (class "Default")
      (node (ref "R38") (pin "2") (pinfunction "2_2") (pintype "passive"))
      (node (ref "U3") (pin "3") (pinfunction "Y6_3") (pintype "bidirectional"))
    )
    (net (code "49") (name "POT39") (class "Default")
      (node (ref "R39") (pin "2") (pinfunction "2_2") (pintype "passive"))
      (node (ref "U3") (pin "8") (pinfunction "Y1_8") (pintype "bidirectional"))
    )
    (net (code "50") (name "POT40") (class "Default")
      (node (ref "R40") (pin "2") (pinfunction "2_2") (pintype "passive"))
      (node (ref "U3") (pin "9") (pinfunction "Y0_9") (pintype "bidirectional"))
    )
    (net (code "51") (name "POT41") (class "Default")
      (node (ref "R41") (pin "2") (pinfunction "2_2") (pintype "passive"))
      (node (ref "U3") (pin "23") (pinfunction "Y8_23") (pintype "bidirectional"))
    )
    (net (code "52") (name "POT42") (class "Default")
      (node (ref "R42") (pin "2") (pinfunction "2_2") (pintype "passive"))
      (node (ref "U3") (pin "22") (pinfunction "Y9_22") (pintype "bidirectional"))
    )
    (net (code "53") (name "POT43") (class "Default")
      (node (ref "R43") (pin "2") (pinfunction "2_2") (pintype "passive"))
      (node (ref "U3") (pin "17") (pinfunction "Y14_17") (pintype "bidirectional"))
    )
    (net (code "54") (name "POT44") (class "Default")
      (node (ref "R44") (pin "2") (pinfunction "2_2") (pintype "passive"))
      (node (ref "U3") (pin "16") (pinfunction "Y15_16") (pintype "bidirectional"))
    )
    (net (code "55") (name "POT45") (class "Default")
      (node (ref "R45") (pin "2") (pinfunction "2_2") (pintype "passive"))
      (node (ref "U3") (pin "21") (pinfunction "Y10_21") (pintype "bidirectional"))
    )
    (net (code "56") (name "POT46") (class "Default")
      (node (ref "R46") (pin "2") (pinfunction "2_2") (pintype "passive"))
      (node (ref "U3") (pin "20") (pinfunction "Y11_20") (pintype "bidirectional"))
    )
    (net (code "57") (name "POT47") (class "Default")
      (node (ref "R47") (pin "2") (pinfunction "2_2") (pintype "passive"))
      (node (ref "U3") (pin "19") (pinfunction "Y12_19") (pintype "bidirectional"))
    )
    (net (code "58") (name "POT48") (class "Default")
      (node (ref "R48") (pin "2") (pinfunction "2_2") (pintype "passive"))
      (node (ref "U3") (pin "18") (pinfunction "Y13_18") (pintype "bidirectional"))
    )
  )
)
